# Clockdistributor.net
KiCad netlist of a schematic drawn in EAGLE
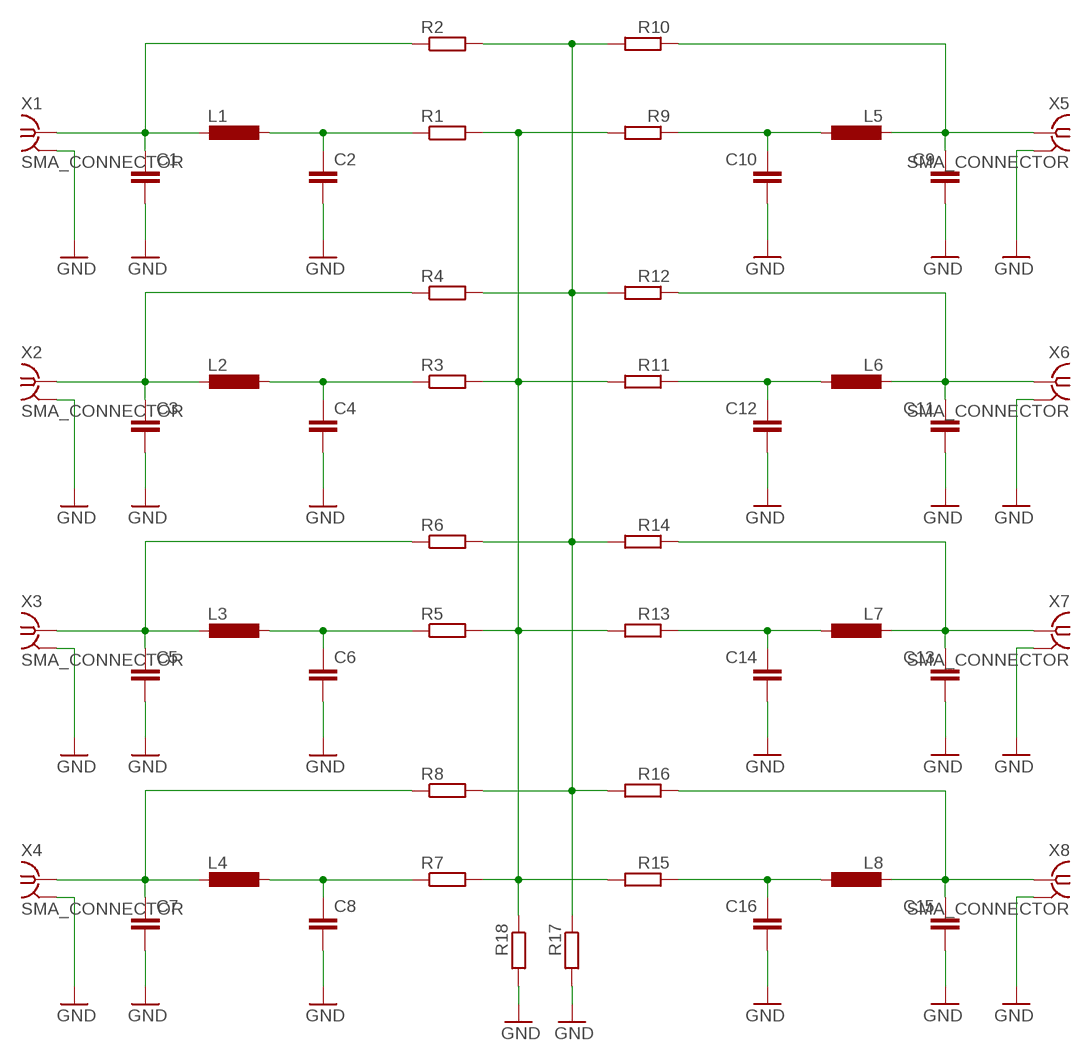
[diagram p0: schematic, sheet 1]

(export (version "E")
  (design (tool "Eeschema 10.0.6"))
  (components
    (comp (ref "C1")
      (value "C-EUC0603")
      (footprint "eagle-import:C0603")
      (libsource (lib "eagle-import") (part "C-EUC0603"))
    )
    (comp (ref "C2")
      (value "C-EUC0603")
      (footprint "eagle-import:C0603")
      (libsource (lib "eagle-import") (part "C-EUC0603"))
    )
    (comp (ref "C3")
      (value "C-EUC0603")
      (footprint "eagle-import:C0603")
      (libsource (lib "eagle-import") (part "C-EUC0603"))
    )
    (comp (ref "C4")
      (value "C-EUC0603")
      (footprint "eagle-import:C0603")
      (libsource (lib "eagle-import") (part "C-EUC0603"))
    )
    (comp (ref "C5")
      (value "C-EUC0603")
      (footprint "eagle-import:C0603")
      (libsource (lib "eagle-import") (part "C-EUC0603"))
    )
    (comp (ref "C6")
      (value "C-EUC0603")
      (footprint "eagle-import:C0603")
      (libsource (lib "eagle-import") (part "C-EUC0603"))
    )
    (comp (ref "C7")
      (value "C-EUC0603")
      (footprint "eagle-import:C0603")
      (libsource (lib "eagle-import") (part "C-EUC0603"))
    )
    (comp (ref "C8")
      (value "C-EUC0603")
      (footprint "eagle-import:C0603")
      (libsource (lib "eagle-import") (part "C-EUC0603"))
    )
    (comp (ref "C9")
      (value "C-EUC0603")
      (footprint "eagle-import:C0603")
      (libsource (lib "eagle-import") (part "C-EUC0603"))
    )
    (comp (ref "C10")
      (value "C-EUC0603")
      (footprint "eagle-import:C0603")
      (libsource (lib "eagle-import") (part "C-EUC0603"))
    )
    (comp (ref "C11")
      (value "C-EUC0603")
      (footprint "eagle-import:C0603")
      (libsource (lib "eagle-import") (part "C-EUC0603"))
    )
    (comp (ref "C12")
      (value "C-EUC0603")
      (footprint "eagle-import:C0603")
      (libsource (lib "eagle-import") (part "C-EUC0603"))
    )
    (comp (ref "C13")
      (value "C-EUC0603")
      (footprint "eagle-import:C0603")
      (libsource (lib "eagle-import") (part "C-EUC0603"))
    )
    (comp (ref "C14")
      (value "C-EUC0603")
      (footprint "eagle-import:C0603")
      (libsource (lib "eagle-import") (part "C-EUC0603"))
    )
    (comp (ref "C15")
      (value "C-EUC0603")
      (footprint "eagle-import:C0603")
      (libsource (lib "eagle-import") (part "C-EUC0603"))
    )
    (comp (ref "C16")
      (value "C-EUC0603")
      (footprint "eagle-import:C0603")
      (libsource (lib "eagle-import") (part "C-EUC0603"))
    )
    (comp (ref "L1")
      (value "L-EUL2012C")
      (footprint "eagle-import:L2012C")
      (libsource (lib "eagle-import") (part "L-EUL2012C"))
    )
    (comp (ref "L2")
      (value "L-EUL2012C")
      (footprint "eagle-import:L2012C")
      (libsource (lib "eagle-import") (part "L-EUL2012C"))
    )
    (comp (ref "L3")
      (value "L-EUL2012C")
      (footprint "eagle-import:L2012C")
      (libsource (lib "eagle-import") (part "L-EUL2012C"))
    )
    (comp (ref "L4")
      (value "L-EUL2012C")
      (footprint "eagle-import:L2012C")
      (libsource (lib "eagle-import") (part "L-EUL2012C"))
    )
    (comp (ref "L5")
      (value "L-EUL2012C")
      (footprint "eagle-import:L2012C")
      (libsource (lib "eagle-import") (part "L-EUL2012C"))
    )
    (comp (ref "L6")
      (value "L-EUL2012C")
      (footprint "eagle-import:L2012C")
      (libsource (lib "eagle-import") (part "L-EUL2012C"))
    )
    (comp (ref "L7")
      (value "L-EUL2012C")
      (footprint "eagle-import:L2012C")
      (libsource (lib "eagle-import") (part "L-EUL2012C"))
    )
    (comp (ref "L8")
      (value "L-EUL2012C")
      (footprint "eagle-import:L2012C")
      (libsource (lib "eagle-import") (part "L-EUL2012C"))
    )
    (comp (ref "R1")
      (value "R-EU_R0603")
      (footprint "eagle-import:R0603")
      (libsource (lib "eagle-import") (part "R-EU_R0603"))
    )
    (comp (ref "R2")
      (value "R-EU_R0603")
      (footprint "eagle-import:R0603")
      (libsource (lib "eagle-import") (part "R-EU_R0603"))
    )
    (comp (ref "R3")
      (value "R-EU_R0603")
      (footprint "eagle-import:R0603")
      (libsource (lib "eagle-import") (part "R-EU_R0603"))
    )
    (comp (ref "R4")
      (value "R-EU_R0603")
      (footprint "eagle-import:R0603")
      (libsource (lib "eagle-import") (part "R-EU_R0603"))
    )
    (comp (ref "R5")
      (value "R-EU_R0603")
      (footprint "eagle-import:R0603")
      (libsource (lib "eagle-import") (part "R-EU_R0603"))
    )
    (comp (ref "R6")
      (value "R-EU_R0603")
      (footprint "eagle-import:R0603")
      (libsource (lib "eagle-import") (part "R-EU_R0603"))
    )
    (comp (ref "R7")
      (value "R-EU_R0603")
      (footprint "eagle-import:R0603")
      (libsource (lib "eagle-import") (part "R-EU_R0603"))
    )
    (comp (ref "R8")
      (value "R-EU_R0603")
      (footprint "eagle-import:R0603")
      (libsource (lib "eagle-import") (part "R-EU_R0603"))
    )
    (comp (ref "R9")
      (value "R-EU_R0603")
      (footprint "eagle-import:R0603")
      (libsource (lib "eagle-import") (part "R-EU_R0603"))
    )
    (comp (ref "R10")
      (value "R-EU_R0603")
      (footprint "eagle-import:R0603")
      (libsource (lib "eagle-import") (part "R-EU_R0603"))
    )
    (comp (ref "R11")
      (value "R-EU_R0603")
      (footprint "eagle-import:R0603")
      (libsource (lib "eagle-import") (part "R-EU_R0603"))
    )
    (comp (ref "R12")
      (value "R-EU_R0603")
      (footprint "eagle-import:R0603")
      (libsource (lib "eagle-import") (part "R-EU_R0603"))
    )
    (comp (ref "R13")
      (value "R-EU_R0603")
      (footprint "eagle-import:R0603")
      (libsource (lib "eagle-import") (part "R-EU_R0603"))
    )
    (comp (ref "R14")
      (value "R-EU_R0603")
      (footprint "eagle-import:R0603")
      (libsource (lib "eagle-import") (part "R-EU_R0603"))
    )
    (comp (ref "R15")
      (value "R-EU_R0603")
      (footprint "eagle-import:R0603")
      (libsource (lib "eagle-import") (part "R-EU_R0603"))
    )
    (comp (ref "R16")
      (value "R-EU_R0603")
      (footprint "eagle-import:R0603")
      (libsource (lib "eagle-import") (part "R-EU_R0603"))
    )
    (comp (ref "R17")
      (value "R-EU_R0603")
      (footprint "eagle-import:R0603")
      (libsource (lib "eagle-import") (part "R-EU_R0603"))
    )
    (comp (ref "R18")
      (value "R-EU_R0603")
      (footprint "eagle-import:R0603")
      (libsource (lib "eagle-import") (part "R-EU_R0603"))
    )
    (comp (ref "X1")
      (value "SMA_CONNECTOR")
      (footprint "eagle-import:J502-ND-142-0711-821_826")
      (libsource (lib "eagle-import") (part "SMA_CONNECTOR"))
    )
    (comp (ref "X2")
      (value "SMA_CONNECTOR")
      (footprint "eagle-import:J502-ND-142-0711-821_826")
      (libsource (lib "eagle-import") (part "SMA_CONNECTOR"))
    )
    (comp (ref "X3")
      (value "SMA_CONNECTOR")
      (footprint "eagle-import:J502-ND-142-0711-821_826")
      (libsource (lib "eagle-import") (part "SMA_CONNECTOR"))
    )
    (comp (ref "X4")
      (value "SMA_CONNECTOR")
      (footprint "eagle-import:J502-ND-142-0711-821_826")
      (libsource (lib "eagle-import") (part "SMA_CONNECTOR"))
    )
    (comp (ref "X5")
      (value "SMA_CONNECTOR")
      (footprint "eagle-import:J502-ND-142-0711-821_826")
      (libsource (lib "eagle-import") (part "SMA_CONNECTOR"))
    )
    (comp (ref "X6")
      (value "SMA_CONNECTOR")
      (footprint "eagle-import:J502-ND-142-0711-821_826")
      (libsource (lib "eagle-import") (part "SMA_CONNECTOR"))
    )
    (comp (ref "X7")
      (value "SMA_CONNECTOR")
      (footprint "eagle-import:J502-ND-142-0711-821_826")
      (libsource (lib "eagle-import") (part "SMA_CONNECTOR"))
    )
    (comp (ref "X8")
      (value "SMA_CONNECTOR")
      (footprint "eagle-import:J502-ND-142-0711-821_826")
      (libsource (lib "eagle-import") (part "SMA_CONNECTOR"))
    )
  )
  (nets
    (net (code "1") (name "GND") (class "Default")
      (node (ref "C1") (pin "2") (pinfunction "2_2") (pintype "passive"))
      (node (ref "C10") (pin "2") (pinfunction "2_2") (pintype "passive"))
      (node (ref "C11") (pin "2") (pinfunction "2_2") (pintype "passive"))
      (node (ref "C12") (pin "2") (pinfunction "2_2") (pintype "passive"))
      (node (ref "C13") (pin "2") (pinfunction "2_2") (pintype "passive"))
      (node (ref "C14") (pin "2") (pinfunction "2_2") (pintype "passive"))
      (node (ref "C15") (pin "2") (pinfunction "2_2") (pintype "passive"))
      (node (ref "C16") (pin "2") (pinfunction "2_2") (pintype "passive"))
      (node (ref "C2") (pin "2") (pinfunction "2_2") (pintype "passive"))
      (node (ref "C3") (pin "2") (pinfunction "2_2") (pintype "passive"))
      (node (ref "C4") (pin "2") (pinfunction "2_2") (pintype "passive"))
      (node (ref "C5") (pin "2") (pinfunction "2_2") (pintype "passive"))
      (node (ref "C6") (pin "2") (pinfunction "2_2") (pintype "passive"))
      (node (ref "C7") (pin "2") (pinfunction "2_2") (pintype "passive"))
      (node (ref "C8") (pin "2") (pinfunction "2_2") (pintype "passive"))
      (node (ref "C9") (pin "2") (pinfunction "2_2") (pintype "passive"))
      (node (ref "R17") (pin "2") (pinfunction "2_2") (pintype "passive"))
      (node (ref "R18") (pin "2") (pinfunction "2_2") (pintype "passive"))
      (node (ref "X1") (pin "G@1") (pinfunction "2_G@1") (pintype "passive"))
      (node (ref "X1") (pin "G@2") (pinfunction "2_G@2") (pintype "passive"))
      (node (ref "X1") (pin "G@3") (pinfunction "2_G@3") (pintype "passive"))
      (node (ref "X1") (pin "G@4") (pinfunction "2_G@4") (pintype "passive"))
      (node (ref "X2") (pin "G@1") (pinfunction "2_G@1") (pintype "passive"))
      (node (ref "X2") (pin "G@2") (pinfunction "2_G@2") (pintype "passive"))
      (node (ref "X2") (pin "G@3") (pinfunction "2_G@3") (pintype "passive"))
      (node (ref "X2") (pin "G@4") (pinfunction "2_G@4") (pintype "passive"))
      (node (ref "X3") (pin "G@1") (pinfunction "2_G@1") (pintype "passive"))
      (node (ref "X3") (pin "G@2") (pinfunction "2_G@2") (pintype "passive"))
      (node (ref "X3") (pin "G@3") (pinfunction "2_G@3") (pintype "passive"))
      (node (ref "X3") (pin "G@4") (pinfunction "2_G@4") (pintype "passive"))
      (node (ref "X4") (pin "G@1") (pinfunction "2_G@1") (pintype "passive"))
      (node (ref "X4") (pin "G@2") (pinfunction "2_G@2") (pintype "passive"))
      (node (ref "X4") (pin "G@3") (pinfunction "2_G@3") (pintype "passive"))
      (node (ref "X4") (pin "G@4") (pinfunction "2_G@4") (pintype "passive"))
      (node (ref "X5") (pin "G@1") (pinfunction "2_G@1") (pintype "passive"))
      (node (ref "X5") (pin "G@2") (pinfunction "2_G@2") (pintype "passive"))
      (node (ref "X5") (pin "G@3") (pinfunction "2_G@3") (pintype "passive"))
      (node (ref "X5") (pin "G@4") (pinfunction "2_G@4") (pintype "passive"))
      (node (ref "X6") (pin "G@1") (pinfunction "2_G@1") (pintype "passive"))
      (node (ref "X6") (pin "G@2") (pinfunction "2_G@2") (pintype "passive"))
      (node (ref "X6") (pin "G@3") (pinfunction "2_G@3") (pintype "passive"))
      (node (ref "X6") (pin "G@4") (pinfunction "2_G@4") (pintype "passive"))
      (node (ref "X7") (pin "G@1") (pinfunction "2_G@1") (pintype "passive"))
      (node (ref "X7") (pin "G@2") (pinfunction "2_G@2") (pintype "passive"))
      (node (ref "X7") (pin "G@3") (pinfunction "2_G@3") (pintype "passive"))
      (node (ref "X7") (pin "G@4") (pinfunction "2_G@4") (pintype "passive"))
      (node (ref "X8") (pin "G@1") (pinfunction "2_G@1") (pintype "passive"))
      (node (ref "X8") (pin "G@2") (pinfunction "2_G@2") (pintype "passive"))
      (node (ref "X8") (pin "G@3") (pinfunction "2_G@3") (pintype "passive"))
      (node (ref "X8") (pin "G@4") (pinfunction "2_G@4") (pintype "passive"))
    )
    (net (code "2") (name "Net-(C1-Pad1)") (class "Default")
      (node (ref "C1") (pin "1") (pinfunction "1_1") (pintype "passive"))
      (node (ref "L1") (pin "2") (pinfunction "2_2") (pintype "passive"))
      (node (ref "R2") (pin "1") (pinfunction "1_1") (pintype "passive"))
      (node (ref "X1") (pin "1") (pinfunction "1_1") (pintype "passive"))
    )
    (net (code "3") (name "Net-(C2-Pad1)") (class "Default")
      (node (ref "C2") (pin "1") (pinfunction "1_1") (pintype "passive"))
      (node (ref "L1") (pin "1") (pinfunction "1_1") (pintype "passive"))
      (node (ref "R1") (pin "1") (pinfunction "1_1") (pintype "passive"))
    )
    (net (code "4") (name "Net-(C3-Pad1)") (class "Default")
      (node (ref "C3") (pin "1") (pinfunction "1_1") (pintype "passive"))
      (node (ref "L2") (pin "2") (pinfunction "2_2") (pintype "passive"))
      (node (ref "R4") (pin "1") (pinfunction "1_1") (pintype "passive"))
      (node (ref "X2") (pin "1") (pinfunction "1_1") (pintype "passive"))
    )
    (net (code "5") (name "Net-(C4-Pad1)") (class "Default")
      (node (ref "C4") (pin "1") (pinfunction "1_1") (pintype "passive"))
      (node (ref "L2") (pin "1") (pinfunction "1_1") (pintype "passive"))
      (node (ref "R3") (pin "1") (pinfunction "1_1") (pintype "passive"))
    )
    (net (code "6") (name "Net-(C5-Pad1)") (class "Default")
      (node (ref "C5") (pin "1") (pinfunction "1_1") (pintype "passive"))
      (node (ref "L3") (pin "2") (pinfunction "2_2") (pintype "passive"))
      (node (ref "R6") (pin "1") (pinfunction "1_1") (pintype "passive"))
      (node (ref "X3") (pin "1") (pinfunction "1_1") (pintype "passive"))
    )
    (net (code "7") (name "Net-(C6-Pad1)") (class "Default")
      (node (ref "C6") (pin "1") (pinfunction "1_1") (pintype "passive"))
      (node (ref "L3") (pin "1") (pinfunction "1_1") (pintype "passive"))
      (node (ref "R5") (pin "1") (pinfunction "1_1") (pintype "passive"))
    )
    (net (code "8") (name "Net-(C7-Pad1)") (class "Default")
      (node (ref "C7") (pin "1") (pinfunction "1_1") (pintype "passive"))
      (node (ref "L4") (pin "2") (pinfunction "2_2") (pintype "passive"))
      (node (ref "R8") (pin "1") (pinfunction "1_1") (pintype "passive"))
      (node (ref "X4") (pin "1") (pinfunction "1_1") (pintype "passive"))
    )
    (net (code "9") (name "Net-(C8-Pad1)") (class "Default")
      (node (ref "C8") (pin "1") (pinfunction "1_1") (pintype "passive"))
      (node (ref "L4") (pin "1") (pinfunction "1_1") (pintype "passive"))
      (node (ref "R7") (pin "1") (pinfunction "1_1") (pintype "passive"))
    )
    (net (code "10") (name "Net-(C9-Pad1)") (class "Default")
      (node (ref "C9") (pin "1") (pinfunction "1_1") (pintype "passive"))
      (node (ref "L5") (pin "2") (pinfunction "2_2") (pintype "passive"))
      (node (ref "R10") (pin "1") (pinfunction "1_1") (pintype "passive"))
      (node (ref "X5") (pin "1") (pinfunction "1_1") (pintype "passive"))
    )
    (net (code "11") (name "Net-(C10-Pad1)") (class "Default")
      (node (ref "C10") (pin "1") (pinfunction "1_1") (pintype "passive"))
      (node (ref "L5") (pin "1") (pinfunction "1_1") (pintype "passive"))
      (node (ref "R9") (pin "1") (pinfunction "1_1") (pintype "passive"))
    )
    (net (code "12") (name "Net-(C11-Pad1)") (class "Default")
      (node (ref "C11") (pin "1") (pinfunction "1_1") (pintype "passive"))
      (node (ref "L6") (pin "2") (pinfunction "2_2") (pintype "passive"))
      (node (ref "R12") (pin "1") (pinfunction "1_1") (pintype "passive"))
      (node (ref "X6") (pin "1") (pinfunction "1_1") (pintype "passive"))
    )
    (net (code "13") (name "Net-(C12-Pad1)") (class "Default")
      (node (ref "C12") (pin "1") (pinfunction "1_1") (pintype "passive"))
      (node (ref "L6") (pin "1") (pinfunction "1_1") (pintype "passive"))
      (node (ref "R11") (pin "1") (pinfunction "1_1") (pintype "passive"))
    )
    (net (code "14") (name "Net-(C13-Pad1)") (class "Default")
      (node (ref "C13") (pin "1") (pinfunction "1_1") (pintype "passive"))
      (node (ref "L7") (pin "2") (pinfunction "2_2") (pintype "passive"))
      (node (ref "R14") (pin "1") (pinfunction "1_1") (pintype "passive"))
      (node (ref "X7") (pin "1") (pinfunction "1_1") (pintype "passive"))
    )
    (net (code "15") (name "Net-(C14-Pad1)") (class "Default")
      (node (ref "C14") (pin "1") (pinfunction "1_1") (pintype "passive"))
      (node (ref "L7") (pin "1") (pinfunction "1_1") (pintype "passive"))
      (node (ref "R13") (pin "1") (pinfunction "1_1") (pintype "passive"))
    )
    (net (code "16") (name "Net-(C15-Pad1)") (class "Default")
      (node (ref "C15") (pin "1") (pinfunction "1_1") (pintype "passive"))
      (node (ref "L8") (pin "2") (pinfunction "2_2") (pintype "passive"))
      (node (ref "R16") (pin "1") (pinfunction "1_1") (pintype "passive"))
      (node (ref "X8") (pin "1") (pinfunction "1_1") (pintype "passive"))
    )
    (net (code "17") (name "Net-(C16-Pad1)") (class "Default")
      (node (ref "C16") (pin "1") (pinfunction "1_1") (pintype "passive"))
      (node (ref "L8") (pin "1") (pinfunction "1_1") (pintype "passive"))
      (node (ref "R15") (pin "1") (pinfunction "1_1") (pintype "passive"))
    )
    (net (code "18") (name "Net-(R1-Pad2)") (class "Default")
      (node (ref "R1") (pin "2") (pinfunction "2_2") (pintype "passive"))
      (node (ref "R11") (pin "2") (pinfunction "2_2") (pintype "passive"))
      (node (ref "R13") (pin "2") (pinfunction "2_2") (pintype "passive"))
      (node (ref "R15") (pin "2") (pinfunction "2_2") (pintype "passive"))
      (node (ref "R18") (pin "1") (pinfunction "1_1") (pintype "passive"))
      (node (ref "R3") (pin "2") (pinfunction "2_2") (pintype "passive"))
      (node (ref "R5") (pin "2") (pinfunction "2_2") (pintype "passive"))
      (node (ref "R7") (pin "2") (pinfunction "2_2") (pintype "passive"))
      (node (ref "R9") (pin "2") (pinfunction "2_2") (pintype "passive"))
    )
    (net (code "19") (name "Net-(R10-Pad2)") (class "Default")
      (node (ref "R10") (pin "2") (pinfunction "2_2") (pintype "passive"))
      (node (ref "R12") (pin "2") (pinfunction "2_2") (pintype "passive"))
      (node (ref "R14") (pin "2") (pinfunction "2_2") (pintype "passive"))
      (node (ref "R16") (pin "2") (pinfunction "2_2") (pintype "passive"))
      (node (ref "R17") (pin "1") (pinfunction "1_1") (pintype "passive"))
      (node (ref "R2") (pin "2") (pinfunction "2_2") (pintype "passive"))
      (node (ref "R4") (pin "2") (pinfunction "2_2") (pintype "passive"))
      (node (ref "R6") (pin "2") (pinfunction "2_2") (pintype "passive"))
      (node (ref "R8") (pin "2") (pinfunction "2_2") (pintype "passive"))
    )
  )
)
